# fpga-bank0-inside.net
KiCad netlist of a schematic drawn in Altium Designer
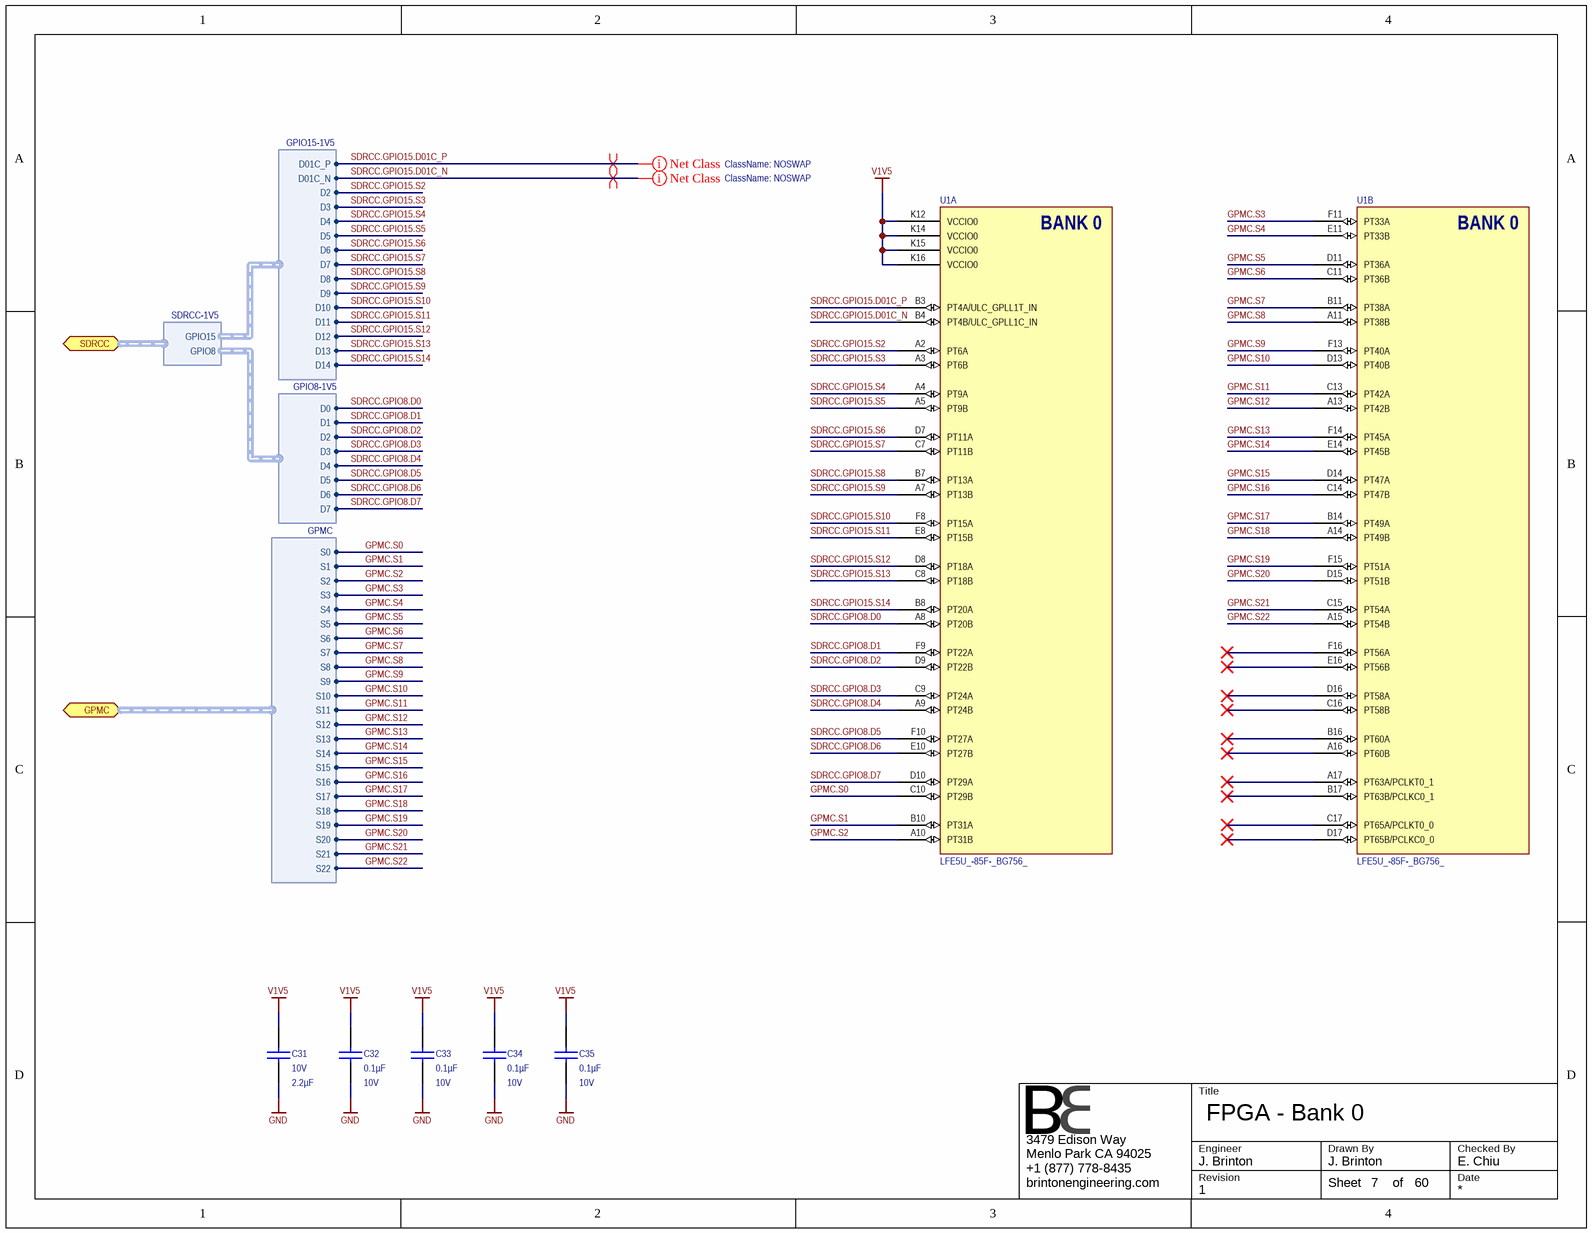
[diagram p0: fpga-bank0-inside.SchDoc]

(export (version "E")
  (design (tool "Eeschema 10.0.6"))
  (components
    (comp (ref "C31")
      (value "GRM188R71A225KE15D")
      (footprint "CAPC1608X90N")
      (description "CAP CER 2.2UF 10V 10% X7R 0603")
      (fields
        (field (name "MANUFACTURER") "Murata Electronics North America")
        (field (name "TOLERANCE") "±10%")
        (field (name "VOLTAGE - RATED") "10V")
        (field (name "CAPACITANCE") "2.2µF")
      )
      (libsource (lib "murata") (part "GRM188R71A225KE15D"))
    )
    (comp (ref "C32")
      (value "GRM155R71A104KA01J")
      (footprint "CAPC1005X56N")
      (description "CAP CER 0.1UF 10V 10% X7R 0402")
      (fields
        (field (name "MANUFACTURER") "Murata Electronics North America")
        (field (name "TOLERANCE") "±10%")
        (field (name "CAPACITANCE") "0.1µF")
        (field (name "VOLTAGE - RATED") "10V")
      )
      (libsource (lib "murata") (part "GRM155R71A104KA01J"))
    )
    (comp (ref "C33")
      (value "GRM155R71A104KA01J")
      (footprint "CAPC1005X56N")
      (description "CAP CER 0.1UF 10V 10% X7R 0402")
      (fields
        (field (name "MANUFACTURER") "Murata Electronics North America")
        (field (name "TOLERANCE") "±10%")
        (field (name "CAPACITANCE") "0.1µF")
        (field (name "VOLTAGE - RATED") "10V")
      )
      (libsource (lib "murata") (part "GRM155R71A104KA01J"))
    )
    (comp (ref "C34")
      (value "GRM155R71A104KA01J")
      (footprint "CAPC1005X56N")
      (description "CAP CER 0.1UF 10V 10% X7R 0402")
      (fields
        (field (name "MANUFACTURER") "Murata Electronics North America")
        (field (name "TOLERANCE") "±10%")
        (field (name "CAPACITANCE") "0.1µF")
        (field (name "VOLTAGE - RATED") "10V")
      )
      (libsource (lib "murata") (part "GRM155R71A104KA01J"))
    )
    (comp (ref "C35")
      (value "GRM155R71A104KA01J")
      (footprint "CAPC1005X56N")
      (description "CAP CER 0.1UF 10V 10% X7R 0402")
      (fields
        (field (name "MANUFACTURER") "Murata Electronics North America")
        (field (name "TOLERANCE") "±10%")
        (field (name "CAPACITANCE") "0.1µF")
        (field (name "VOLTAGE - RATED") "10V")
      )
      (libsource (lib "murata") (part "GRM155R71A104KA01J"))
    )
    (comp (ref "U1")
      (value "LFE5U_-85F-_BG756_")
      (footprint "lattice:caBGA756")
      (description "ECP5 FPGA, 85k LUT, 756-caBGA")
      (fields (field (name "MANUFACTURER") "Lattice Semiconductor"))
      (libsource (lib "lattice") (part "LFE5U_-85F-_BG756_"))
    )
  )
  (nets
    (net (code "4") (name "/GPMC.S0") (class "Default")
      (node (ref "U1") (pin "C10") (pinfunction "PT29B_C10") (pintype "bidirectional"))
    )
    (net (code "5") (name "/GPMC.S1") (class "Default")
      (node (ref "U1") (pin "B10") (pinfunction "PT31A_B10") (pintype "bidirectional"))
    )
    (net (code "6") (name "/GPMC.S2") (class "Default")
      (node (ref "U1") (pin "A10") (pinfunction "PT31B_A10") (pintype "bidirectional"))
    )
    (net (code "7") (name "/GPMC.S3") (class "Default")
      (node (ref "U1") (pin "F11") (pinfunction "PT33A_F11") (pintype "bidirectional"))
    )
    (net (code "8") (name "/GPMC.S4") (class "Default")
      (node (ref "U1") (pin "E11") (pinfunction "PT33B_E11") (pintype "bidirectional"))
    )
    (net (code "9") (name "/GPMC.S5") (class "Default")
      (node (ref "U1") (pin "D11") (pinfunction "PT36A_D11") (pintype "bidirectional"))
    )
    (net (code "10") (name "/GPMC.S6") (class "Default")
      (node (ref "U1") (pin "C11") (pinfunction "PT36B_C11") (pintype "bidirectional"))
    )
    (net (code "11") (name "/GPMC.S7") (class "Default")
      (node (ref "U1") (pin "B11") (pinfunction "PT38A_B11") (pintype "bidirectional"))
    )
    (net (code "12") (name "/GPMC.S8") (class "Default")
      (node (ref "U1") (pin "A11") (pinfunction "PT38B_A11") (pintype "bidirectional"))
    )
    (net (code "13") (name "/GPMC.S9") (class "Default")
      (node (ref "U1") (pin "F13") (pinfunction "PT40A_F13") (pintype "bidirectional"))
    )
    (net (code "14") (name "/GPMC.S10") (class "Default")
      (node (ref "U1") (pin "D13") (pinfunction "PT40B_D13") (pintype "bidirectional"))
    )
    (net (code "15") (name "/GPMC.S11") (class "Default")
      (node (ref "U1") (pin "C13") (pinfunction "PT42A_C13") (pintype "bidirectional"))
    )
    (net (code "16") (name "/GPMC.S12") (class "Default")
      (node (ref "U1") (pin "A13") (pinfunction "PT42B_A13") (pintype "bidirectional"))
    )
    (net (code "17") (name "/GPMC.S13") (class "Default")
      (node (ref "U1") (pin "F14") (pinfunction "PT45A_F14") (pintype "bidirectional"))
    )
    (net (code "18") (name "/GPMC.S14") (class "Default")
      (node (ref "U1") (pin "E14") (pinfunction "PT45B_E14") (pintype "bidirectional"))
    )
    (net (code "19") (name "/GPMC.S15") (class "Default")
      (node (ref "U1") (pin "D14") (pinfunction "PT47A_D14") (pintype "bidirectional"))
    )
    (net (code "20") (name "/GPMC.S16") (class "Default")
      (node (ref "U1") (pin "C14") (pinfunction "PT47B_C14") (pintype "bidirectional"))
    )
    (net (code "21") (name "/GPMC.S17") (class "Default")
      (node (ref "U1") (pin "B14") (pinfunction "PT49A_B14") (pintype "bidirectional"))
    )
    (net (code "22") (name "/GPMC.S18") (class "Default")
      (node (ref "U1") (pin "A14") (pinfunction "PT49B_A14") (pintype "bidirectional"))
    )
    (net (code "23") (name "/GPMC.S19") (class "Default")
      (node (ref "U1") (pin "F15") (pinfunction "PT51A_F15") (pintype "bidirectional"))
    )
    (net (code "24") (name "/GPMC.S20") (class "Default")
      (node (ref "U1") (pin "D15") (pinfunction "PT51B_D15") (pintype "bidirectional"))
    )
    (net (code "25") (name "/GPMC.S21") (class "Default")
      (node (ref "U1") (pin "C15") (pinfunction "PT54A_C15") (pintype "bidirectional"))
    )
    (net (code "26") (name "/GPMC.S22") (class "Default")
      (node (ref "U1") (pin "A15") (pinfunction "PT54B_A15") (pintype "bidirectional"))
    )
    (net (code "27") (name "/SDRCC.GPIO8.D0") (class "Default")
      (node (ref "U1") (pin "A8") (pinfunction "PT20B_A8") (pintype "bidirectional"))
    )
    (net (code "28") (name "/SDRCC.GPIO8.D1") (class "Default")
      (node (ref "U1") (pin "F9") (pinfunction "PT22A_F9") (pintype "bidirectional"))
    )
    (net (code "29") (name "/SDRCC.GPIO8.D2") (class "Default")
      (node (ref "U1") (pin "D9") (pinfunction "PT22B_D9") (pintype "bidirectional"))
    )
    (net (code "30") (name "/SDRCC.GPIO8.D3") (class "Default")
      (node (ref "U1") (pin "C9") (pinfunction "PT24A_C9") (pintype "bidirectional"))
    )
    (net (code "31") (name "/SDRCC.GPIO8.D4") (class "Default")
      (node (ref "U1") (pin "A9") (pinfunction "PT24B_A9") (pintype "bidirectional"))
    )
    (net (code "32") (name "/SDRCC.GPIO8.D5") (class "Default")
      (node (ref "U1") (pin "F10") (pinfunction "PT27A_F10") (pintype "bidirectional"))
    )
    (net (code "33") (name "/SDRCC.GPIO8.D6") (class "Default")
      (node (ref "U1") (pin "E10") (pinfunction "PT27B_E10") (pintype "bidirectional"))
    )
    (net (code "34") (name "/SDRCC.GPIO8.D7") (class "Default")
      (node (ref "U1") (pin "D10") (pinfunction "PT29A_D10") (pintype "bidirectional"))
    )
    (net (code "35") (name "/SDRCC.GPIO15.D01C_N") (class "Default")
      (node (ref "U1") (pin "B4") (pinfunction "PT4B/ULC_GPLL1C_IN_B4") (pintype "bidirectional"))
    )
    (net (code "36") (name "/SDRCC.GPIO15.D01C_P") (class "Default")
      (node (ref "U1") (pin "B3") (pinfunction "PT4A/ULC_GPLL1T_IN_B3") (pintype "bidirectional"))
    )
    (net (code "37") (name "/SDRCC.GPIO15.S2") (class "Default")
      (node (ref "U1") (pin "A2") (pinfunction "PT6A_A2") (pintype "bidirectional"))
    )
    (net (code "38") (name "/SDRCC.GPIO15.S3") (class "Default")
      (node (ref "U1") (pin "A3") (pinfunction "PT6B_A3") (pintype "bidirectional"))
    )
    (net (code "39") (name "/SDRCC.GPIO15.S4") (class "Default")
      (node (ref "U1") (pin "A4") (pinfunction "PT9A_A4") (pintype "bidirectional"))
    )
    (net (code "40") (name "/SDRCC.GPIO15.S5") (class "Default")
      (node (ref "U1") (pin "A5") (pinfunction "PT9B_A5") (pintype "bidirectional"))
    )
    (net (code "41") (name "/SDRCC.GPIO15.S6") (class "Default")
      (node (ref "U1") (pin "D7") (pinfunction "PT11A_D7") (pintype "bidirectional"))
    )
    (net (code "42") (name "/SDRCC.GPIO15.S7") (class "Default")
      (node (ref "U1") (pin "C7") (pinfunction "PT11B_C7") (pintype "bidirectional"))
    )
    (net (code "43") (name "/SDRCC.GPIO15.S8") (class "Default")
      (node (ref "U1") (pin "B7") (pinfunction "PT13A_B7") (pintype "bidirectional"))
    )
    (net (code "44") (name "/SDRCC.GPIO15.S9") (class "Default")
      (node (ref "U1") (pin "A7") (pinfunction "PT13B_A7") (pintype "bidirectional"))
    )
    (net (code "45") (name "/SDRCC.GPIO15.S10") (class "Default")
      (node (ref "U1") (pin "F8") (pinfunction "PT15A_F8") (pintype "bidirectional"))
    )
    (net (code "46") (name "/SDRCC.GPIO15.S11") (class "Default")
      (node (ref "U1") (pin "E8") (pinfunction "PT15B_E8") (pintype "bidirectional"))
    )
    (net (code "47") (name "/SDRCC.GPIO15.S12") (class "Default")
      (node (ref "U1") (pin "D8") (pinfunction "PT18A_D8") (pintype "bidirectional"))
    )
    (net (code "48") (name "/SDRCC.GPIO15.S13") (class "Default")
      (node (ref "U1") (pin "C8") (pinfunction "PT18B_C8") (pintype "bidirectional"))
    )
    (net (code "49") (name "/SDRCC.GPIO15.S14") (class "Default")
      (node (ref "U1") (pin "B8") (pinfunction "PT20A_B8") (pintype "bidirectional"))
    )
    (net (code "53") (name "GND") (class "Default")
      (node (ref "C31") (pin "1") (pinfunction "1_1") (pintype "passive"))
      (node (ref "C32") (pin "1") (pinfunction "1_1") (pintype "passive"))
      (node (ref "C33") (pin "1") (pinfunction "1_1") (pintype "passive"))
      (node (ref "C34") (pin "1") (pinfunction "1_1") (pintype "passive"))
      (node (ref "C35") (pin "1") (pinfunction "1_1") (pintype "passive"))
    )
    (net (code "54") (name "V1V5") (class "Default")
      (node (ref "C31") (pin "2") (pinfunction "2_2") (pintype "passive"))
      (node (ref "C32") (pin "2") (pinfunction "2_2") (pintype "passive"))
      (node (ref "C33") (pin "2") (pinfunction "2_2") (pintype "passive"))
      (node (ref "C34") (pin "2") (pinfunction "2_2") (pintype "passive"))
      (node (ref "C35") (pin "2") (pinfunction "2_2") (pintype "passive"))
      (node (ref "U1") (pin "K12") (pinfunction "VCCIO0_K12") (pintype "power_in"))
      (node (ref "U1") (pin "K14") (pinfunction "VCCIO0_K14") (pintype "power_in"))
      (node (ref "U1") (pin "K15") (pinfunction "VCCIO0_K15") (pintype "power_in"))
      (node (ref "U1") (pin "K16") (pinfunction "VCCIO0_K16") (pintype "power_in"))
    )
    (net (code "55") (name "unconnected-(U1B-PT56A-PadF16)") (class "Default")
      (node (ref "U1") (pin "F16") (pinfunction "PT56A_F16") (pintype "bidirectional+no_connect"))
    )
    (net (code "56") (name "unconnected-(U1B-PT56B-PadE16)") (class "Default")
      (node (ref "U1") (pin "E16") (pinfunction "PT56B_E16") (pintype "bidirectional+no_connect"))
    )
    (net (code "57") (name "unconnected-(U1B-PT58A-PadD16)") (class "Default")
      (node (ref "U1") (pin "D16") (pinfunction "PT58A_D16") (pintype "bidirectional+no_connect"))
    )
    (net (code "58") (name "unconnected-(U1B-PT58B-PadC16)") (class "Default")
      (node (ref "U1") (pin "C16") (pinfunction "PT58B_C16") (pintype "bidirectional+no_connect"))
    )
    (net (code "59") (name "unconnected-(U1B-PT60A-PadB16)") (class "Default")
      (node (ref "U1") (pin "B16") (pinfunction "PT60A_B16") (pintype "bidirectional+no_connect"))
    )
    (net (code "60") (name "unconnected-(U1B-PT60B-PadA16)") (class "Default")
      (node (ref "U1") (pin "A16") (pinfunction "PT60B_A16") (pintype "bidirectional+no_connect"))
    )
    (net (code "61") (name "unconnected-(U1B-PT63A{slash}PCLKT0_1-PadA17)") (class "Default")
      (node (ref "U1") (pin "A17") (pinfunction "PT63A/PCLKT0_1_A17") (pintype "bidirectional+no_connect"))
    )
    (net (code "62") (name "unconnected-(U1B-PT63B{slash}PCLKC0_1-PadB17)") (class "Default")
      (node (ref "U1") (pin "B17") (pinfunction "PT63B/PCLKC0_1_B17") (pintype "bidirectional+no_connect"))
    )
    (net (code "63") (name "unconnected-(U1B-PT65A{slash}PCLKT0_0-PadC17)") (class "Default")
      (node (ref "U1") (pin "C17") (pinfunction "PT65A/PCLKT0_0_C17") (pintype "bidirectional+no_connect"))
    )
    (net (code "64") (name "unconnected-(U1B-PT65B{slash}PCLKC0_0-PadD17)") (class "Default")
      (node (ref "U1") (pin "D17") (pinfunction "PT65B/PCLKC0_0_D17") (pintype "bidirectional+no_connect"))
    )
  )
)
